# Skramzer.net
KiCad netlist of a schematic drawn in EAGLE
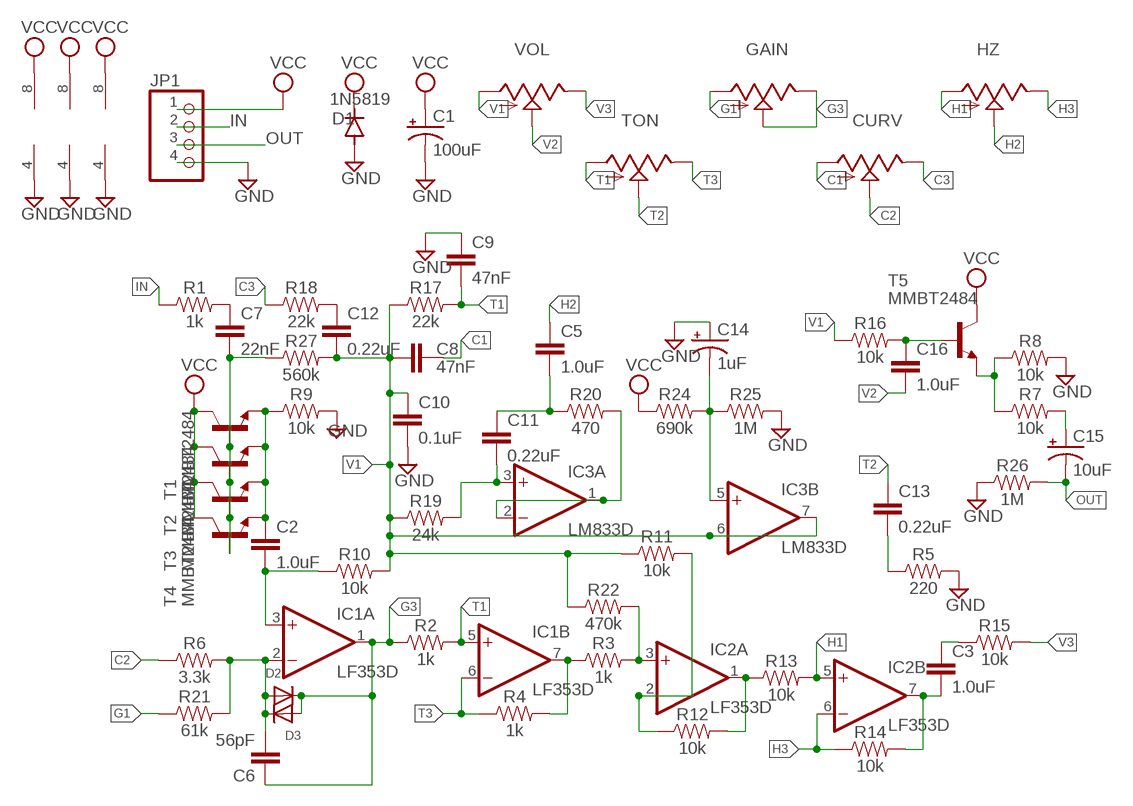
[diagram p0: schematic, sheet 1]

(export (version "E")
  (design (tool "Eeschema 10.0.6"))
  (components
    (comp (ref "C1")
      (value "100uF")
      (footprint "eagle-import:PAN_B_SMD+THRU")
      (libsource (lib "eagle-import") (part "CAP_SMD+THRUPAN_B"))
    )
    (comp (ref "C2")
      (value "1.0uF")
      (footprint "eagle-import:0603")
      (libsource (lib "eagle-import") (part "1.0UF-0603-16V-10%"))
    )
    (comp (ref "C3")
      (value "1.0uF")
      (footprint "eagle-import:0603")
      (libsource (lib "eagle-import") (part "1.0UF-0603-16V-10%"))
    )
    (comp (ref "C5")
      (value "1.0uF")
      (footprint "eagle-import:0603")
      (libsource (lib "eagle-import") (part "1.0UF-0603-16V-10%"))
    )
    (comp (ref "C6")
      (value "56pF")
      (footprint "eagle-import:0603")
      (libsource (lib "eagle-import") (part "33PF-0603-50V-5%"))
    )
    (comp (ref "C7")
      (value "22nF")
      (footprint "eagle-import:0603")
      (libsource (lib "eagle-import") (part "22NF/22,000PF-0603-50V-10%"))
    )
    (comp (ref "C8")
      (value "47nF")
      (footprint "eagle-import:0603")
      (libsource (lib "eagle-import") (part "47NF-0603-25V-5%"))
    )
    (comp (ref "C9")
      (value "47nF")
      (footprint "eagle-import:0603")
      (libsource (lib "eagle-import") (part "47NF-0603-25V-5%"))
    )
    (comp (ref "C10")
      (value "0.1uF")
      (footprint "eagle-import:0603")
      (libsource (lib "eagle-import") (part "0.1UF-0603-25V-(+80/-20%)"))
    )
    (comp (ref "C11")
      (value "0.22uF")
      (footprint "eagle-import:0603")
      (libsource (lib "eagle-import") (part "0.22UF-0603-25V-10%"))
    )
    (comp (ref "C12")
      (value "0.22uF")
      (footprint "eagle-import:0603")
      (libsource (lib "eagle-import") (part "0.22UF-0603-25V-10%"))
    )
    (comp (ref "C13")
      (value "0.22uF")
      (footprint "eagle-import:0603")
      (libsource (lib "eagle-import") (part "0.22UF-0603-25V-10%"))
    )
    (comp (ref "C14")
      (value "1uF")
      (footprint "eagle-import:PAN_B_SMD+THRU")
      (libsource (lib "eagle-import") (part "CAP_SMD+THRUPAN_B"))
    )
    (comp (ref "C15")
      (value "10uF")
      (footprint "eagle-import:PAN_B_SMD+THRU")
      (libsource (lib "eagle-import") (part "CAP_SMD+THRUPAN_B"))
    )
    (comp (ref "C16")
      (value "1.0uF")
      (footprint "eagle-import:0603")
      (libsource (lib "eagle-import") (part "1.0UF-0603-16V-10%"))
    )
    (comp (ref "CURV")
      (value "9MM_SNAP-IN_POT_")
      (footprint "eagle-import:9MM_SNAP-IN_POT")
      (libsource (lib "eagle-import") (part "9MM_SNAP-IN_POT_"))
    )
    (comp (ref "D1")
      (value "1N5819")
      (footprint "eagle-import:SOD123")
      (libsource (lib "eagle-import") (part "DIODE-SOD123"))
    )
    (comp (ref "D2")
      (value "DIODESOD-123")
      (footprint "eagle-import:SOD-123")
      (libsource (lib "eagle-import") (part "DIODESOD-123"))
    )
    (comp (ref "D3")
      (value "DIODESOD-123")
      (footprint "eagle-import:SOD-123")
      (libsource (lib "eagle-import") (part "DIODESOD-123"))
    )
    (comp (ref "GAIN")
      (value "9MM_SNAP-IN_POT_")
      (footprint "eagle-import:9MM_SNAP-IN_POT")
      (libsource (lib "eagle-import") (part "9MM_SNAP-IN_POT_"))
    )
    (comp (ref "HZ")
      (value "9MM_SNAP-IN_POT_")
      (footprint "eagle-import:9MM_SNAP-IN_POT")
      (libsource (lib "eagle-import") (part "9MM_SNAP-IN_POT_"))
    )
    (comp (ref "IC1")
      (value "LF353D")
      (footprint "eagle-import:SO08")
      (libsource (lib "eagle-import") (part "LF353D"))
    )
    (comp (ref "IC2")
      (value "LF353D")
      (footprint "eagle-import:SO08")
      (libsource (lib "eagle-import") (part "LF353D"))
    )
    (comp (ref "IC3")
      (value "LM833D")
      (footprint "eagle-import:SO08")
      (libsource (lib "eagle-import") (part "LM833D"))
    )
    (comp (ref "JP1")
      (value "PINHD-1X4")
      (footprint "eagle-import:1X04")
      (libsource (lib "eagle-import") (part "PINHD-1X4"))
    )
    (comp (ref "R1")
      (value "1k")
      (footprint "eagle-import:0603")
      (libsource (lib "eagle-import") (part "1KOHM-0603-1/10W-1%"))
    )
    (comp (ref "R2")
      (value "1k")
      (footprint "eagle-import:0603")
      (libsource (lib "eagle-import") (part "1KOHM-0603-1/10W-1%"))
    )
    (comp (ref "R3")
      (value "1k")
      (footprint "eagle-import:0603")
      (libsource (lib "eagle-import") (part "1KOHM-0603-1/10W-1%"))
    )
    (comp (ref "R4")
      (value "1k")
      (footprint "eagle-import:0603")
      (libsource (lib "eagle-import") (part "1KOHM-0603-1/10W-1%"))
    )
    (comp (ref "R5")
      (value "220")
      (footprint "eagle-import:0603")
      (libsource (lib "eagle-import") (part "220OHM-0603-1/10W-1%"))
    )
    (comp (ref "R6")
      (value "3.3k")
      (footprint "eagle-import:0603")
      (libsource (lib "eagle-import") (part "3.3KOHM-0603-1/10W-1%"))
    )
    (comp (ref "R7")
      (value "10k")
      (footprint "eagle-import:0603")
      (libsource (lib "eagle-import") (part "10KOHM-0603-1/10W-1%"))
    )
    (comp (ref "R8")
      (value "10k")
      (footprint "eagle-import:0603")
      (libsource (lib "eagle-import") (part "10KOHM-0603-1/10W-1%"))
    )
    (comp (ref "R9")
      (value "10k")
      (footprint "eagle-import:0603")
      (libsource (lib "eagle-import") (part "10KOHM-0603-1/10W-1%"))
    )
    (comp (ref "R10")
      (value "10k")
      (footprint "eagle-import:0603")
      (libsource (lib "eagle-import") (part "10KOHM-0603-1/10W-1%"))
    )
    (comp (ref "R11")
      (value "10k")
      (footprint "eagle-import:0603")
      (libsource (lib "eagle-import") (part "10KOHM-0603-1/10W-1%"))
    )
    (comp (ref "R12")
      (value "10k")
      (footprint "eagle-import:0603")
      (libsource (lib "eagle-import") (part "10KOHM-0603-1/10W-1%"))
    )
    (comp (ref "R13")
      (value "10k")
      (footprint "eagle-import:0603")
      (libsource (lib "eagle-import") (part "10KOHM-0603-1/10W-1%"))
    )
    (comp (ref "R14")
      (value "10k")
      (footprint "eagle-import:0603")
      (libsource (lib "eagle-import") (part "10KOHM-0603-1/10W-1%"))
    )
    (comp (ref "R15")
      (value "10k")
      (footprint "eagle-import:0603")
      (libsource (lib "eagle-import") (part "10KOHM-0603-1/10W-1%"))
    )
    (comp (ref "R16")
      (value "10k")
      (footprint "eagle-import:0603")
      (libsource (lib "eagle-import") (part "10KOHM-0603-1/10W-1%"))
    )
    (comp (ref "R17")
      (value "22k")
      (footprint "eagle-import:0603")
      (libsource (lib "eagle-import") (part "22KOHM-0603-1/10W-1%"))
    )
    (comp (ref "R18")
      (value "22k")
      (footprint "eagle-import:0603")
      (libsource (lib "eagle-import") (part "22KOHM-0603-1/10W-1%"))
    )
    (comp (ref "R19")
      (value "24k")
      (footprint "eagle-import:0603")
      (libsource (lib "eagle-import") (part "22KOHM-0603-1/10W-1%"))
    )
    (comp (ref "R20")
      (value "470")
      (footprint "eagle-import:0603")
      (libsource (lib "eagle-import") (part "470OHM-0603-1/10W-1%"))
    )
    (comp (ref "R21")
      (value "61k")
      (footprint "eagle-import:0603")
      (libsource (lib "eagle-import") (part "62KOHM-0603-1/10W-5%"))
    )
    (comp (ref "R22")
      (value "470k")
      (footprint "eagle-import:0603")
      (libsource (lib "eagle-import") (part "470OHM-0603-1/10W-1%"))
    )
    (comp (ref "R24")
      (value "690k")
      (footprint "eagle-import:0603")
      (libsource (lib "eagle-import") (part "680OHM-0603-1/10W-5%"))
    )
    (comp (ref "R25")
      (value "1M")
      (footprint "eagle-import:0603")
      (libsource (lib "eagle-import") (part "1MOHM-0603-1/4W-5%"))
    )
    (comp (ref "R26")
      (value "1M")
      (footprint "eagle-import:0603")
      (libsource (lib "eagle-import") (part "1MOHM-0603-1/4W-5%"))
    )
    (comp (ref "R27")
      (value "560k")
      (footprint "eagle-import:0603")
      (libsource (lib "eagle-import") (part "330KOHM-0603-1/10W-1%"))
    )
    (comp (ref "T1")
      (value "MMBT2484")
      (footprint "eagle-import:SOT23-BEC")
      (libsource (lib "eagle-import") (part "-NPN-SOT23-BECMMBT2484LT1"))
    )
    (comp (ref "T2")
      (value "MMBT2484")
      (footprint "eagle-import:SOT23-BEC")
      (libsource (lib "eagle-import") (part "-NPN-SOT23-BECMMBT2484LT1"))
    )
    (comp (ref "T3")
      (value "MMBT2484")
      (footprint "eagle-import:SOT23-BEC")
      (libsource (lib "eagle-import") (part "-NPN-SOT23-BECMMBT2484LT1"))
    )
    (comp (ref "T4")
      (value "MMBT2484")
      (footprint "eagle-import:SOT23-BEC")
      (libsource (lib "eagle-import") (part "-NPN-SOT23-BECMMBT2484LT1"))
    )
    (comp (ref "T5")
      (value "MMBT2484")
      (footprint "eagle-import:SOT23-BEC")
      (libsource (lib "eagle-import") (part "-NPN-SOT23-BECMMBT2484LT1"))
    )
    (comp (ref "TON")
      (value "9MM_SNAP-IN_POT_")
      (footprint "eagle-import:9MM_SNAP-IN_POT")
      (libsource (lib "eagle-import") (part "9MM_SNAP-IN_POT_"))
    )
    (comp (ref "VOL")
      (value "9MM_SNAP-IN_POT_")
      (footprint "eagle-import:9MM_SNAP-IN_POT")
      (libsource (lib "eagle-import") (part "9MM_SNAP-IN_POT_"))
    )
  )
  (nets
    (net (code "1") (name "C1") (class "Default")
      (node (ref "C8") (pin "1") (pinfunction "1_1") (pintype "passive"))
      (node (ref "CURV") (pin "1") (pinfunction "A_1") (pintype "passive"))
    )
    (net (code "2") (name "C2") (class "Default")
      (node (ref "CURV") (pin "2") (pinfunction "S_2") (pintype "passive"))
      (node (ref "R6") (pin "1") (pinfunction "1_1") (pintype "passive"))
    )
    (net (code "3") (name "C3") (class "Default")
      (node (ref "CURV") (pin "3") (pinfunction "E_3") (pintype "passive"))
      (node (ref "R18") (pin "1") (pinfunction "1_1") (pintype "passive"))
    )
    (net (code "4") (name "G1") (class "Default")
      (node (ref "GAIN") (pin "1") (pinfunction "A_1") (pintype "passive"))
      (node (ref "R21") (pin "1") (pinfunction "1_1") (pintype "passive"))
    )
    (net (code "5") (name "G3") (class "Default")
      (node (ref "C6") (pin "1") (pinfunction "1_1") (pintype "passive"))
      (node (ref "D2") (pin "C") (pinfunction "C_C") (pintype "passive"))
      (node (ref "D3") (pin "A") (pinfunction "A_A") (pintype "passive"))
      (node (ref "GAIN") (pin "2") (pinfunction "S_2") (pintype "passive"))
      (node (ref "GAIN") (pin "3") (pinfunction "E_3") (pintype "passive"))
      (node (ref "IC1") (pin "1") (pinfunction "OUT_1") (pintype "output"))
      (node (ref "R2") (pin "1") (pinfunction "1_1") (pintype "passive"))
    )
    (net (code "6") (name "GND") (class "Default")
      (node (ref "C1") (pin "-") (pinfunction "-_-") (pintype "passive"))
      (node (ref "C1") (pin "--") (pinfunction "-_--") (pintype "passive"))
      (node (ref "C10") (pin "2") (pinfunction "2_2") (pintype "passive"))
      (node (ref "C14") (pin "+") (pinfunction "+_+") (pintype "passive"))
      (node (ref "C14") (pin "++") (pinfunction "+_++") (pintype "passive"))
      (node (ref "C9") (pin "1") (pinfunction "1_1") (pintype "passive"))
      (node (ref "D1") (pin "A") (pinfunction "A_A") (pintype "passive"))
      (node (ref "IC1") (pin "4") (pinfunction "V-_4") (pintype "power_in"))
      (node (ref "IC2") (pin "4") (pinfunction "V-_4") (pintype "power_in"))
      (node (ref "IC3") (pin "4") (pinfunction "V-_4") (pintype "power_in"))
      (node (ref "JP1") (pin "4") (pinfunction "4_4") (pintype "passive"))
      (node (ref "R25") (pin "2") (pinfunction "2_2") (pintype "passive"))
      (node (ref "R26") (pin "1") (pinfunction "1_1") (pintype "passive"))
      (node (ref "R5") (pin "2") (pinfunction "2_2") (pintype "passive"))
      (node (ref "R8") (pin "2") (pinfunction "2_2") (pintype "passive"))
      (node (ref "R9") (pin "2") (pinfunction "2_2") (pintype "passive"))
    )
    (net (code "7") (name "H1") (class "Default")
      (node (ref "HZ") (pin "1") (pinfunction "A_1") (pintype "passive"))
      (node (ref "IC2") (pin "5") (pinfunction "+IN_5") (pintype "input"))
      (node (ref "R13") (pin "2") (pinfunction "2_2") (pintype "passive"))
    )
    (net (code "8") (name "H2") (class "Default")
      (node (ref "C5") (pin "1") (pinfunction "1_1") (pintype "passive"))
      (node (ref "HZ") (pin "2") (pinfunction "S_2") (pintype "passive"))
    )
    (net (code "9") (name "H3") (class "Default")
      (node (ref "HZ") (pin "3") (pinfunction "E_3") (pintype "passive"))
      (node (ref "IC2") (pin "6") (pinfunction "-IN_6") (pintype "input"))
      (node (ref "R14") (pin "1") (pinfunction "1_1") (pintype "passive"))
    )
    (net (code "10") (name "IN") (class "Default")
      (node (ref "JP1") (pin "2") (pinfunction "2_2") (pintype "passive"))
      (node (ref "R1") (pin "1") (pinfunction "1_1") (pintype "passive"))
    )
    (net (code "11") (name "Net-(C2-Pad1)") (class "Default")
      (node (ref "C2") (pin "1") (pinfunction "1_1") (pintype "passive"))
      (node (ref "R9") (pin "1") (pinfunction "1_1") (pintype "passive"))
      (node (ref "T1") (pin "E") (pinfunction "E_E") (pintype "passive"))
      (node (ref "T2") (pin "E") (pinfunction "E_E") (pintype "passive"))
      (node (ref "T3") (pin "E") (pinfunction "E_E") (pintype "passive"))
      (node (ref "T4") (pin "E") (pinfunction "E_E") (pintype "passive"))
    )
    (net (code "12") (name "Net-(C3-Pad1)") (class "Default")
      (node (ref "C3") (pin "1") (pinfunction "1_1") (pintype "passive"))
      (node (ref "R15") (pin "1") (pinfunction "1_1") (pintype "passive"))
    )
    (net (code "13") (name "Net-(C7-Pad1)") (class "Default")
      (node (ref "C7") (pin "1") (pinfunction "1_1") (pintype "passive"))
      (node (ref "R1") (pin "2") (pinfunction "2_2") (pintype "passive"))
    )
    (net (code "14") (name "Net-(C7-Pad2)") (class "Default")
      (node (ref "C7") (pin "2") (pinfunction "2_2") (pintype "passive"))
      (node (ref "R27") (pin "1") (pinfunction "1_1") (pintype "passive"))
      (node (ref "T1") (pin "B") (pinfunction "B_B") (pintype "passive"))
      (node (ref "T2") (pin "B") (pinfunction "B_B") (pintype "passive"))
      (node (ref "T3") (pin "B") (pinfunction "B_B") (pintype "passive"))
      (node (ref "T4") (pin "B") (pinfunction "B_B") (pintype "passive"))
    )
    (net (code "15") (name "Net-(C11-Pad1)") (class "Default")
      (node (ref "C11") (pin "1") (pinfunction "1_1") (pintype "passive"))
      (node (ref "C5") (pin "2") (pinfunction "2_2") (pintype "passive"))
      (node (ref "R20") (pin "1") (pinfunction "1_1") (pintype "passive"))
    )
    (net (code "16") (name "Net-(C12-Pad1)") (class "Default")
      (node (ref "C12") (pin "1") (pinfunction "1_1") (pintype "passive"))
      (node (ref "R18") (pin "2") (pinfunction "2_2") (pintype "passive"))
    )
    (net (code "17") (name "Net-(C13-Pad2)") (class "Default")
      (node (ref "C13") (pin "2") (pinfunction "2_2") (pintype "passive"))
      (node (ref "R5") (pin "1") (pinfunction "1_1") (pintype "passive"))
    )
    (net (code "18") (name "Net-(C15-+-Pad++)") (class "Default")
      (node (ref "C15") (pin "+") (pinfunction "+_+") (pintype "passive"))
      (node (ref "C15") (pin "++") (pinfunction "+_++") (pintype "passive"))
      (node (ref "R7") (pin "2") (pinfunction "2_2") (pintype "passive"))
    )
    (net (code "19") (name "Net-(C16-Pad1)") (class "Default")
      (node (ref "C16") (pin "1") (pinfunction "1_1") (pintype "passive"))
      (node (ref "R16") (pin "2") (pinfunction "2_2") (pintype "passive"))
      (node (ref "T5") (pin "B") (pinfunction "B_B") (pintype "passive"))
    )
    (net (code "20") (name "Net-(IC1A-+IN)") (class "Default")
      (node (ref "C2") (pin "2") (pinfunction "2_2") (pintype "passive"))
      (node (ref "IC1") (pin "3") (pinfunction "+IN_3") (pintype "input"))
      (node (ref "R10") (pin "1") (pinfunction "1_1") (pintype "passive"))
    )
    (net (code "21") (name "Net-(IC1A--IN)") (class "Default")
      (node (ref "C6") (pin "2") (pinfunction "2_2") (pintype "passive"))
      (node (ref "D2") (pin "A") (pinfunction "A_A") (pintype "passive"))
      (node (ref "D3") (pin "C") (pinfunction "C_C") (pintype "passive"))
      (node (ref "IC1") (pin "2") (pinfunction "-IN_2") (pintype "input"))
      (node (ref "R21") (pin "2") (pinfunction "2_2") (pintype "passive"))
      (node (ref "R6") (pin "2") (pinfunction "2_2") (pintype "passive"))
    )
    (net (code "22") (name "Net-(IC1B-OUT)") (class "Default")
      (node (ref "IC1") (pin "7") (pinfunction "OUT_7") (pintype "output"))
      (node (ref "R3") (pin "1") (pinfunction "1_1") (pintype "passive"))
      (node (ref "R4") (pin "2") (pinfunction "2_2") (pintype "passive"))
    )
    (net (code "23") (name "Net-(IC2A-+IN)") (class "Default")
      (node (ref "IC2") (pin "3") (pinfunction "+IN_3") (pintype "input"))
      (node (ref "R22") (pin "2") (pinfunction "2_2") (pintype "passive"))
      (node (ref "R3") (pin "2") (pinfunction "2_2") (pintype "passive"))
    )
    (net (code "24") (name "Net-(IC2A--IN)") (class "Default")
      (node (ref "IC2") (pin "2") (pinfunction "-IN_2") (pintype "input"))
      (node (ref "R11") (pin "2") (pinfunction "2_2") (pintype "passive"))
      (node (ref "R12") (pin "1") (pinfunction "1_1") (pintype "passive"))
    )
    (net (code "25") (name "Net-(IC2A-OUT)") (class "Default")
      (node (ref "IC2") (pin "1") (pinfunction "OUT_1") (pintype "output"))
      (node (ref "R12") (pin "2") (pinfunction "2_2") (pintype "passive"))
      (node (ref "R13") (pin "1") (pinfunction "1_1") (pintype "passive"))
    )
    (net (code "26") (name "Net-(IC2B-OUT)") (class "Default")
      (node (ref "C3") (pin "2") (pinfunction "2_2") (pintype "passive"))
      (node (ref "IC2") (pin "7") (pinfunction "OUT_7") (pintype "output"))
      (node (ref "R14") (pin "2") (pinfunction "2_2") (pintype "passive"))
    )
    (net (code "27") (name "Net-(IC3A-+IN)") (class "Default")
      (node (ref "C11") (pin "2") (pinfunction "2_2") (pintype "passive"))
      (node (ref "IC3") (pin "3") (pinfunction "+IN_3") (pintype "input"))
      (node (ref "R19") (pin "2") (pinfunction "2_2") (pintype "passive"))
    )
    (net (code "28") (name "Net-(IC3A--IN)") (class "Default")
      (node (ref "IC3") (pin "1") (pinfunction "OUT_1") (pintype "output"))
      (node (ref "IC3") (pin "2") (pinfunction "-IN_2") (pintype "input"))
      (node (ref "R20") (pin "2") (pinfunction "2_2") (pintype "passive"))
    )
    (net (code "29") (name "Net-(IC3B-+IN)") (class "Default")
      (node (ref "C14") (pin "-") (pinfunction "-_-") (pintype "passive"))
      (node (ref "C14") (pin "--") (pinfunction "-_--") (pintype "passive"))
      (node (ref "IC3") (pin "5") (pinfunction "+IN_5") (pintype "input"))
      (node (ref "R24") (pin "2") (pinfunction "2_2") (pintype "passive"))
      (node (ref "R25") (pin "1") (pinfunction "1_1") (pintype "passive"))
    )
    (net (code "30") (name "Net-(R7-Pad1)") (class "Default")
      (node (ref "R7") (pin "1") (pinfunction "1_1") (pintype "passive"))
      (node (ref "R8") (pin "1") (pinfunction "1_1") (pintype "passive"))
      (node (ref "T5") (pin "E") (pinfunction "E_E") (pintype "passive"))
    )
    (net (code "31") (name "OUT") (class "Default")
      (node (ref "C15") (pin "-") (pinfunction "-_-") (pintype "passive"))
      (node (ref "C15") (pin "--") (pinfunction "-_--") (pintype "passive"))
      (node (ref "JP1") (pin "3") (pinfunction "3_3") (pintype "passive"))
      (node (ref "R26") (pin "2") (pinfunction "2_2") (pintype "passive"))
    )
    (net (code "32") (name "T1") (class "Default")
      (node (ref "C9") (pin "2") (pinfunction "2_2") (pintype "passive"))
      (node (ref "IC1") (pin "5") (pinfunction "+IN_5") (pintype "input"))
      (node (ref "R17") (pin "2") (pinfunction "2_2") (pintype "passive"))
      (node (ref "R2") (pin "2") (pinfunction "2_2") (pintype "passive"))
      (node (ref "TON") (pin "1") (pinfunction "A_1") (pintype "passive"))
    )
    (net (code "33") (name "T2") (class "Default")
      (node (ref "C13") (pin "1") (pinfunction "1_1") (pintype "passive"))
      (node (ref "TON") (pin "2") (pinfunction "S_2") (pintype "passive"))
    )
    (net (code "34") (name "T3") (class "Default")
      (node (ref "IC1") (pin "6") (pinfunction "-IN_6") (pintype "input"))
      (node (ref "R4") (pin "1") (pinfunction "1_1") (pintype "passive"))
      (node (ref "TON") (pin "3") (pinfunction "E_3") (pintype "passive"))
    )
    (net (code "35") (name "V1") (class "Default")
      (node (ref "C10") (pin "1") (pinfunction "1_1") (pintype "passive"))
      (node (ref "C12") (pin "2") (pinfunction "2_2") (pintype "passive"))
      (node (ref "C8") (pin "2") (pinfunction "2_2") (pintype "passive"))
      (node (ref "IC3") (pin "6") (pinfunction "-IN_6") (pintype "input"))
      (node (ref "IC3") (pin "7") (pinfunction "OUT_7") (pintype "output"))
      (node (ref "R10") (pin "2") (pinfunction "2_2") (pintype "passive"))
      (node (ref "R11") (pin "1") (pinfunction "1_1") (pintype "passive"))
      (node (ref "R16") (pin "1") (pinfunction "1_1") (pintype "passive"))
      (node (ref "R17") (pin "1") (pinfunction "1_1") (pintype "passive"))
      (node (ref "R19") (pin "1") (pinfunction "1_1") (pintype "passive"))
      (node (ref "R22") (pin "1") (pinfunction "1_1") (pintype "passive"))
      (node (ref "R27") (pin "2") (pinfunction "2_2") (pintype "passive"))
      (node (ref "VOL") (pin "1") (pinfunction "A_1") (pintype "passive"))
    )
    (net (code "36") (name "V2") (class "Default")
      (node (ref "C16") (pin "2") (pinfunction "2_2") (pintype "passive"))
      (node (ref "VOL") (pin "2") (pinfunction "S_2") (pintype "passive"))
    )
    (net (code "37") (name "V3") (class "Default")
      (node (ref "R15") (pin "2") (pinfunction "2_2") (pintype "passive"))
      (node (ref "VOL") (pin "3") (pinfunction "E_3") (pintype "passive"))
    )
    (net (code "38") (name "VCC") (class "Default")
      (node (ref "C1") (pin "+") (pinfunction "+_+") (pintype "passive"))
      (node (ref "C1") (pin "++") (pinfunction "+_++") (pintype "passive"))
      (node (ref "D1") (pin "C") (pinfunction "C_C") (pintype "passive"))
      (node (ref "IC1") (pin "8") (pinfunction "V+_8") (pintype "power_in"))
      (node (ref "IC2") (pin "8") (pinfunction "V+_8") (pintype "power_in"))
      (node (ref "IC3") (pin "8") (pinfunction "V+_8") (pintype "power_in"))
      (node (ref "JP1") (pin "1") (pinfunction "1_1") (pintype "passive"))
      (node (ref "R24") (pin "1") (pinfunction "1_1") (pintype "passive"))
      (node (ref "T1") (pin "C") (pinfunction "C_C") (pintype "passive"))
      (node (ref "T2") (pin "C") (pinfunction "C_C") (pintype "passive"))
      (node (ref "T3") (pin "C") (pinfunction "C_C") (pintype "passive"))
      (node (ref "T4") (pin "C") (pinfunction "C_C") (pintype "passive"))
      (node (ref "T5") (pin "C") (pinfunction "C_C") (pintype "passive"))
    )
  )
)
